# LT3798.net
KiCad netlist of a schematic drawn in Altium Designer
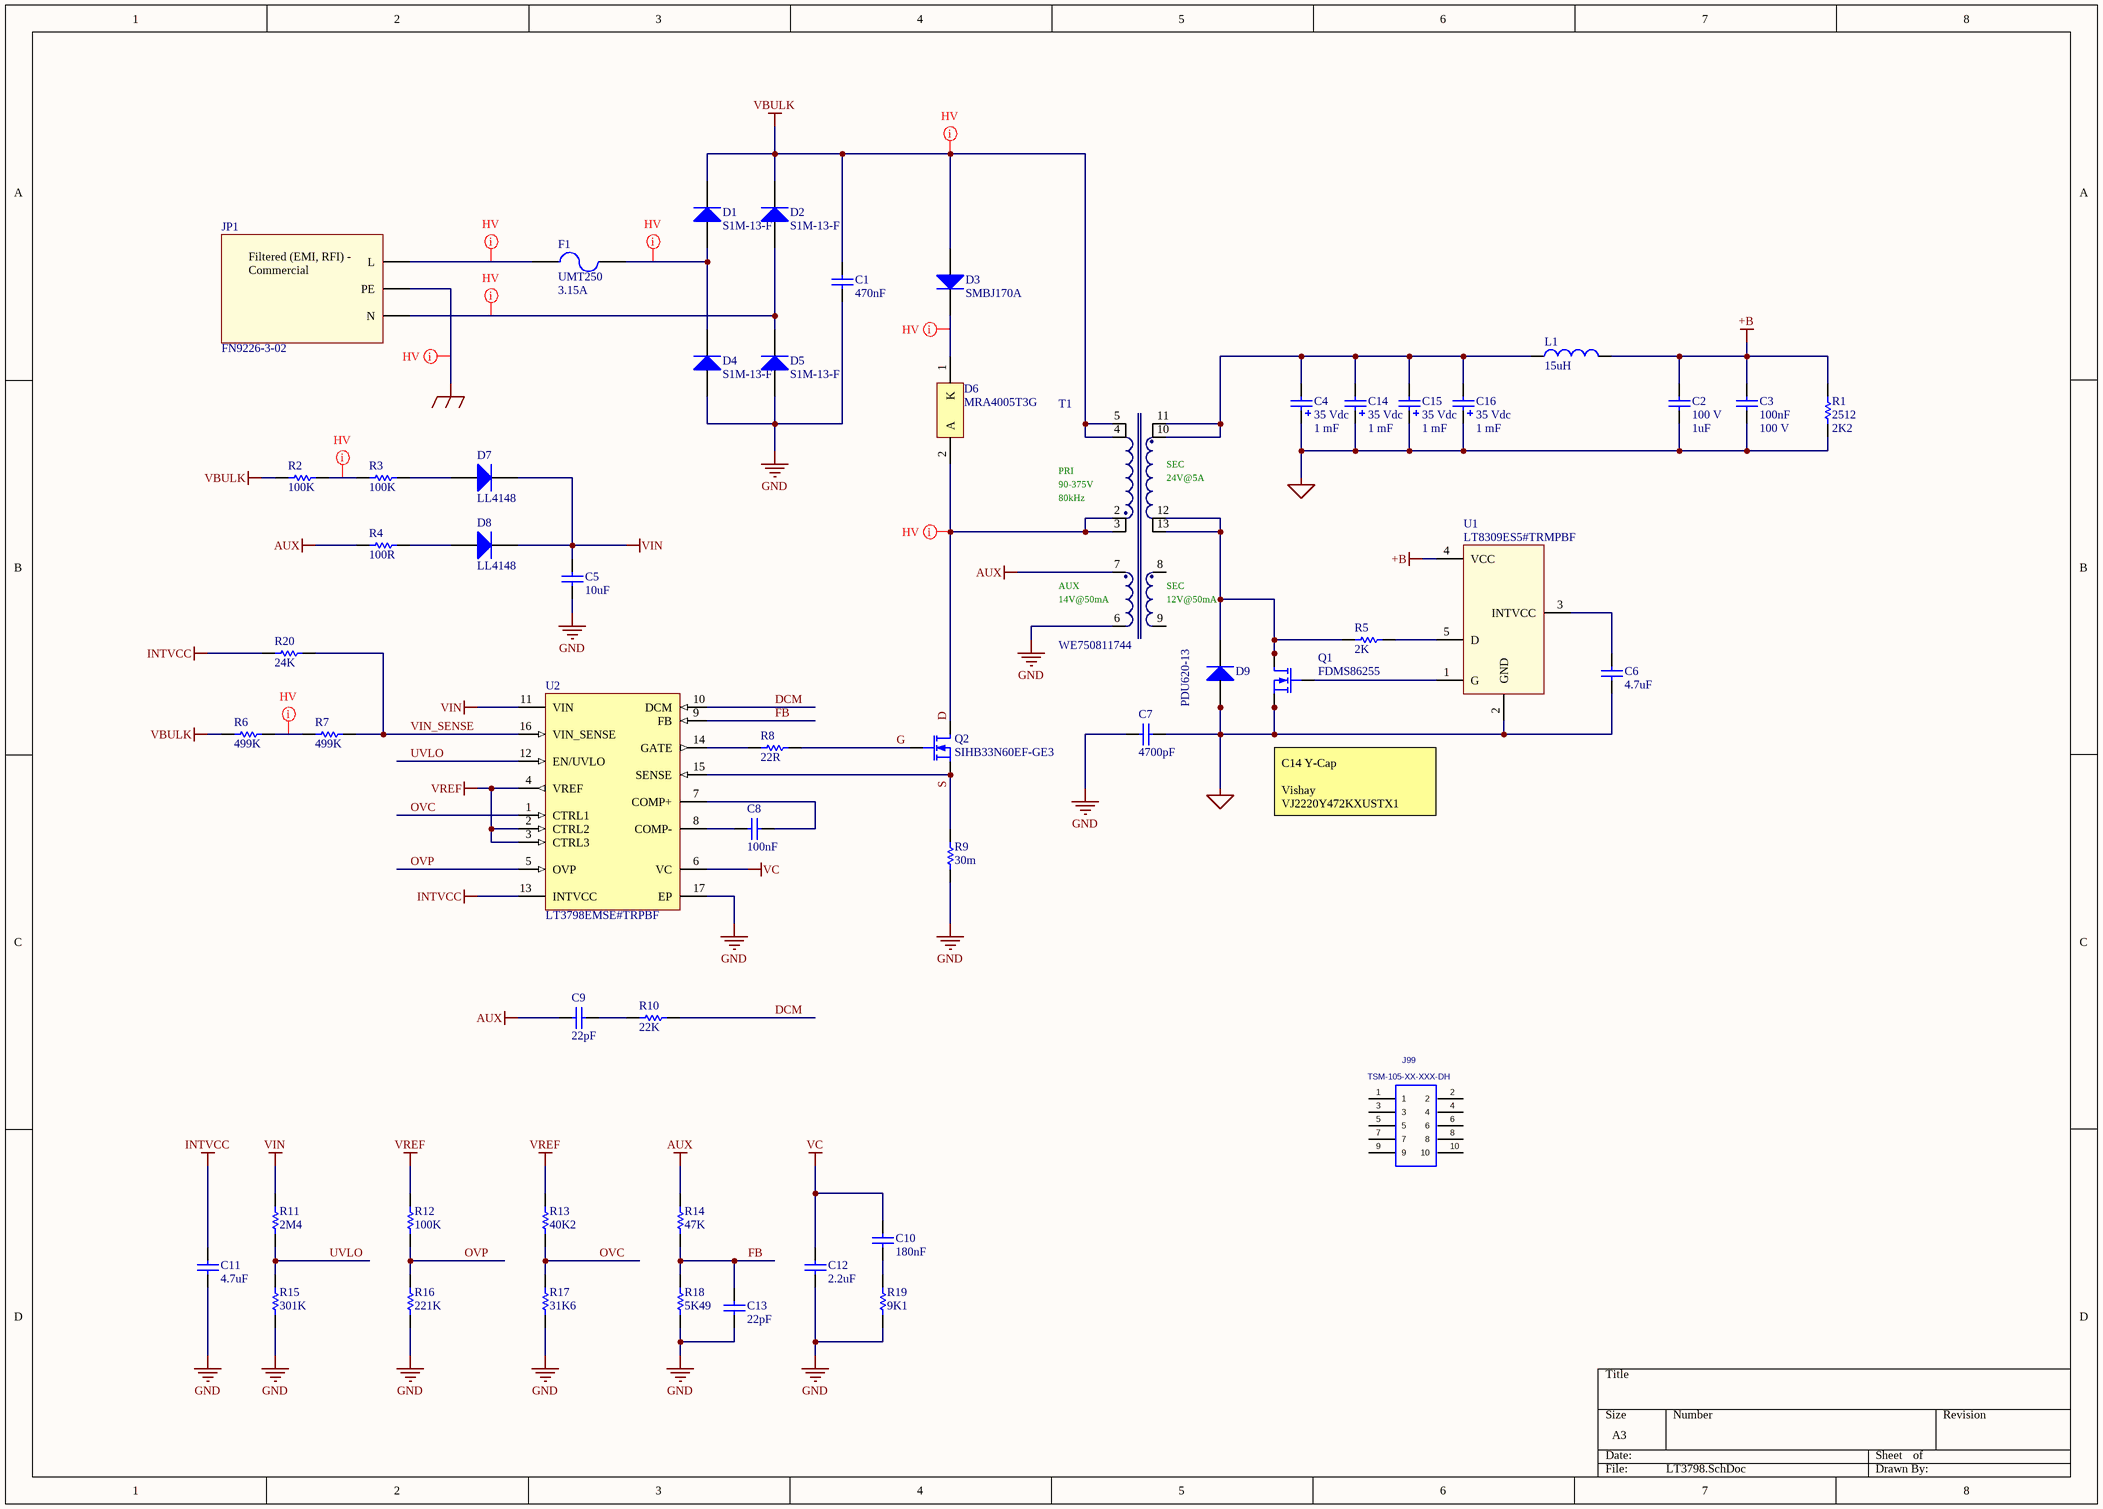
[diagram p0: LT3798.SchDoc]

(export (version "E")
  (design (tool "Eeschema 10.0.6"))
  (components
    (comp (ref "C1")
      (value "470nF")
      (footprint "CAP_RM15_W9L18")
      (description "CAP FILM 0.47UF 400VDC RADIAL")
      (fields (field (name "MPN") "B32652A4474J189"))
      (libsource (lib "micun") (part "CAP_FILM_470NF_400V"))
    )
    (comp (ref "C2")
      (value "1uF")
      (footprint "CAPC1206(3216)190_L")
      (description "CAP 1uF 100V ±20% 1206 (3216 Metric) Thickness 1.9mm SMD")
      (fields
        (field (name "RATED VOLTAGE") "100 V")
        (field (name "TOLERANCE") "Â±20%")
        (field (name "Comment") "CAP 1uF 100V 1206(3216)")
      )
      (libsource (lib "Altium Content Vault") (part "CAP"))
    )
    (comp (ref "C3")
      (value "100nF")
      (footprint "CAPC1206(3216)150_M")
      (description "CAP 100nF 100V ±20% 1206 (3216 Metric) Thickness 1.45mm SMD")
      (fields
        (field (name "TOLERANCE") "Â±20%")
        (field (name "RATED VOLTAGE") "100 V")
        (field (name "Comment") "CAP 100nF 100V 1206(3216)")
      )
      (libsource (lib "Altium Content Vault") (part "CAP"))
    )
    (comp (ref "C4")
      (value "1 mF")
      (footprint "WCAP-ATLL_10x30x5")
      (description "WCAP-ATLL Aluminum Electrolytic Capacitors, 10x30mm, 35 Vdc, 1 mF")
      (fields
        (field (name "PART NUMBER") "860160575031")
        (field (name "RATED VOLTAGE") "35 Vdc")
        (field (name "Comment") "35 Vdc, 1 mF")
        (field (name "PUBLISHER") "Wurth Elektronik")
      )
      (libsource (lib "ALTIUM-WCAP-ATLL-rev17a") (part "860160575031"))
    )
    (comp (ref "C5")
      (value "10uF")
      (footprint "CAPC0805(2012)75_N")
      (description "Generic capacitor non polarised")
      (fields (field (name "Comment") "CAP"))
      (libsource (lib "micun") (part "CAP"))
    )
    (comp (ref "C6")
      (value "4.7uF")
      (footprint "CAPC0805(2012)75_N")
      (description "Generic capacitor non polarised")
      (fields (field (name "Comment") "CAP"))
      (libsource (lib "micun") (part "CAP"))
    )
    (comp (ref "C7")
      (value "4700pF")
      (footprint "CAP_VY2472M49Y5US63V7")
      (description "4700pF ±20% 440VAC Ceramic Capacitor Y5U (E) Radial, Disc")
      (fields (field (name "MPN") "VY2472M49Y5US63V7") (field (name "VOLTAGE") "440VAC"))
      (libsource (lib "micun") (part "CAP_VY2_4700"))
    )
    (comp (ref "C8")
      (value "100nF")
      (footprint "CAPC0805(2012)75_N")
      (description "Generic capacitor non polarised")
      (fields (field (name "Comment") "CAP"))
      (libsource (lib "micun") (part "CAP"))
    )
    (comp (ref "C9")
      (value "22pF")
      (footprint "CAPC0805(2012)75_N")
      (description "Generic capacitor non polarised")
      (fields (field (name "Comment") "CAP"))
      (libsource (lib "micun") (part "CAP"))
    )
    (comp (ref "C10")
      (value "180nF")
      (footprint "CAPC0805(2012)75_N")
      (description "Generic capacitor non polarised")
      (fields (field (name "Comment") "CAP"))
      (libsource (lib "micun") (part "CAP"))
    )
    (comp (ref "C11")
      (value "4.7uF")
      (footprint "CAPC0805(2012)75_N")
      (description "Generic capacitor non polarised")
      (fields (field (name "Comment") "CAP"))
      (libsource (lib "micun") (part "CAP"))
    )
    (comp (ref "C12")
      (value "2.2uF")
      (footprint "CAPC0805(2012)75_N")
      (description "Generic capacitor non polarised")
      (fields (field (name "Comment") "CAP"))
      (libsource (lib "micun") (part "CAP"))
    )
    (comp (ref "C13")
      (value "22pF")
      (footprint "CAPC0805(2012)75_N")
      (description "Generic capacitor non polarised")
      (fields (field (name "Comment") "CAP"))
      (libsource (lib "micun") (part "CAP"))
    )
    (comp (ref "C14")
      (value "1 mF")
      (footprint "WCAP-ATLL_10x30x5")
      (description "WCAP-ATLL Aluminum Electrolytic Capacitors, 10x30mm, 35 Vdc, 1 mF")
      (fields
        (field (name "PART NUMBER") "860160575031")
        (field (name "RATED VOLTAGE") "35 Vdc")
        (field (name "Comment") "35 Vdc, 1 mF")
        (field (name "PUBLISHER") "Wurth Elektronik")
      )
      (libsource (lib "ALTIUM-WCAP-ATLL-rev17a") (part "860160575031"))
    )
    (comp (ref "C15")
      (value "1 mF")
      (footprint "WCAP-ATLL_10x30x5")
      (description "WCAP-ATLL Aluminum Electrolytic Capacitors, 10x30mm, 35 Vdc, 1 mF")
      (fields
        (field (name "PART NUMBER") "860160575031")
        (field (name "RATED VOLTAGE") "35 Vdc")
        (field (name "Comment") "35 Vdc, 1 mF")
        (field (name "PUBLISHER") "Wurth Elektronik")
      )
      (libsource (lib "ALTIUM-WCAP-ATLL-rev17a") (part "860160575031"))
    )
    (comp (ref "C16")
      (value "1 mF")
      (footprint "WCAP-ATLL_10x30x5")
      (description "WCAP-ATLL Aluminum Electrolytic Capacitors, 10x30mm, 35 Vdc, 1 mF")
      (fields
        (field (name "PART NUMBER") "860160575031")
        (field (name "RATED VOLTAGE") "35 Vdc")
        (field (name "Comment") "35 Vdc, 1 mF")
        (field (name "PUBLISHER") "Wurth Elektronik")
      )
      (libsource (lib "ALTIUM-WCAP-ATLL-rev17a") (part "860160575031"))
    )
    (comp (ref "D1")
      (value "S1M-13-F")
      (footprint "DIOD-S1M-13-F-SMA-2_V")
      (fields (field (name "MANUFACTURER") "Diodes Inc"))
      (libsource (lib "Altium Content Vault") (part "DIOD-D-A1K2-2"))
    )
    (comp (ref "D2")
      (value "S1M-13-F")
      (footprint "DIOD-S1M-13-F-SMA-2_V")
      (fields (field (name "MANUFACTURER") "Diodes Inc"))
      (libsource (lib "Altium Content Vault") (part "DIOD-D-A1K2-2"))
    )
    (comp (ref "D3")
      (value "SMBJ170A")
      (footprint "FAIR-DO-214AA-2_V")
      (description "TVS DIODE 170V 353V SMB")
      (fields (field (name "MANUFACTURER") "Fairchild Semiconductor"))
      (libsource (lib "micun") (part "TVS-SMBJ170A"))
    )
    (comp (ref "D4")
      (value "S1M-13-F")
      (footprint "DIOD-S1M-13-F-SMA-2_V")
      (fields (field (name "MANUFACTURER") "Diodes Inc"))
      (libsource (lib "Altium Content Vault") (part "DIOD-D-A1K2-2"))
    )
    (comp (ref "D5")
      (value "S1M-13-F")
      (footprint "DIOD-S1M-13-F-SMA-2_V")
      (fields (field (name "MANUFACTURER") "Diodes Inc"))
      (libsource (lib "Altium Content Vault") (part "DIOD-D-A1K2-2"))
    )
    (comp (ref "D6")
      (value "MRA4005T3G")
      (footprint "ONSC-SMA-2-403D-02_V")
      (description "Surface Mount Standard Recovery Power Rectifier, 2-Pin SMA, Pb-Free, Tape and Reel")
      (fields (field (name "MANUFACTURER") "On Semiconductor"))
      (libsource (lib "Altium Content Vault") (part "ONSC-D-K1A2-2_A"))
    )
    (comp (ref "D7")
      (value "LL4148")
      (footprint "DIOD-SOD-80")
      (description "DIODE GEN PURP 100V 200MA SOD80")
      (libsource (lib "micun") (part "DIOD_GP_LL4148"))
    )
    (comp (ref "D8")
      (value "LL4148")
      (footprint "DIOD-SOD-80")
      (description "DIODE GEN PURP 100V 200MA SOD80")
      (libsource (lib "micun") (part "DIOD_GP_LL4148"))
    )
    (comp (ref "D9")
      (value "PDU620-13")
      (footprint "PowerDI5")
      (description "Diode Standard 200V 6A Surface Mount PowerDI™ 5")
      (libsource (lib "micun") (part "DIOD_GP_PDU620-13"))
    )
    (comp (ref "F1")
      (value "UMT250")
      (footprint "FUSE_UMT250")
      (description "Fuse")
      (fields (field (name "MPN") "3403.0171.11") (field (name "ALTIUM_VALUE") "3.15A"))
      (libsource (lib "micun") (part "FUSE_UMT250-3.15A"))
    )
    (comp (ref "J99")
      (value "TSM-105-XX-XXX-DH")
      (footprint "TSM-105-XX-XXX-DH")
      (description "Terminal Strip, Dual Row Horizontal, Surface Mount, 0.100\" Pitch, 10 Pins.")
      (fields (field (name "MANUFACTURER") "SAMTEC") (field (name "CREATED") "July 11, 2014 - Wendy Xin"))
      (libsource (lib "micun") (part "CONN-TSM-105-XX-XXX-DH"))
    )
    (comp (ref "JP1")
      (value "FN9226-3-02")
      (footprint "CONN-FN9226-3-02")
      (libsource (lib "micun") (part "CONN_FN9226-3-02"))
    )
    (comp (ref "L1")
      (value "15uH")
      (footprint "1D14A")
      (description "Fixed Inductors Class D Inductor 15uH 16mOhms")
      (fields (field (name "MPN") "1D14A-150m"))
      (libsource (lib "micun") (part "L-1D14A-150m"))
    )
    (comp (ref "Q1")
      (value "FDMS86255")
      (footprint "POWER56")
      (description "N-Channel 150V 10A (Ta), 45A (Tc) 2.7W (Ta), 113W (Tc) Surface Mount Power56")
      (libsource (lib "micun") (part "TRAN_FDMS86255"))
    )
    (comp (ref "Q2")
      (value "SIHB33N60EF-GE3")
      (footprint "D2PAK_L")
      (description "N-Channel 600V 33A (Tc) 278W (Tc) Surface Mount D²PAK (TO-263)")
      (libsource (lib "micun") (part "TRAN_SIHB33N60EF-GE3"))
    )
    (comp (ref "R1")
      (value "2K2")
      (footprint "RESC2512(6432)_L")
      (description "2K2 1W 5% 2512 (6432 Metric)  SMD")
      (fields (field (name "POWER") "1 W") (field (name "CASE-EIA") "2512") (field (name "TOLERANCE") "5 %"))
      (libsource (lib "Altium Content Vault") (part "RES"))
    )
    (comp (ref "R2")
      (value "100K")
      (footprint "RESC1206(3216)_L")
      (description "100K 0.25W 1% 1206 (3216 Metric)  SMD")
      (fields (field (name "TOLERANCE") "1 %") (field (name "POWER") "0.25 W"))
      (libsource (lib "Altium Content Vault") (part "RES"))
    )
    (comp (ref "R3")
      (value "100K")
      (footprint "RESC1206(3216)_L")
      (description "100K 0.25W 1% 1206 (3216 Metric)  SMD")
      (fields (field (name "TOLERANCE") "1 %") (field (name "POWER") "0.25 W"))
      (libsource (lib "Altium Content Vault") (part "RES"))
    )
    (comp (ref "R4")
      (value "100R")
      (footprint "RESC0805(2012)_N")
      (description "Generic resistor")
      (fields (field (name "Comment") "RES"))
      (libsource (lib "micun") (part "RES"))
    )
    (comp (ref "R5")
      (value "2K")
      (footprint "RESC0805(2012)_N")
      (description "Generic resistor")
      (fields (field (name "Comment") "RES"))
      (libsource (lib "micun") (part "RES"))
    )
    (comp (ref "R6")
      (value "499K")
      (footprint "RESC1206(3216)_L")
      (description "499K 0.25W 1% 1206 (3216 Metric)  SMD")
      (fields (field (name "TOLERANCE") "1 %") (field (name "POWER") "0.25 W"))
      (libsource (lib "Altium Content Vault") (part "RES"))
    )
    (comp (ref "R7")
      (value "499K")
      (footprint "RESC1206(3216)_L")
      (description "499K 0.25W 1% 1206 (3216 Metric)  SMD")
      (fields (field (name "TOLERANCE") "1 %") (field (name "POWER") "0.25 W"))
      (libsource (lib "Altium Content Vault") (part "RES"))
    )
    (comp (ref "R8")
      (value "22R")
      (footprint "RESC0805(2012)_L")
      (description "22R 0.125W 5% 0805 (2012 Metric)  SMD")
      (fields (field (name "POWER") "0.125 W") (field (name "TOLERANCE") "5 %"))
      (libsource (lib "Altium Content Vault") (part "RES"))
    )
    (comp (ref "R9")
      (value "30m")
      (footprint "RESC1206(3216)_N")
      (description "Generic resistor")
      (fields (field (name "Comment") "RES"))
      (libsource (lib "micun") (part "RES"))
    )
    (comp (ref "R10")
      (value "22K")
      (footprint "RESC0805(2012)_L")
      (description "22K 0.125W 5% 0805 (2012 Metric)  SMD")
      (fields (field (name "POWER") "0.125 W") (field (name "TOLERANCE") "5 %"))
      (libsource (lib "Altium Content Vault") (part "RES"))
    )
    (comp (ref "R11")
      (value "2M4")
      (footprint "RESC0805(2012)_L")
      (description "2M4 0.125W 1% 0805 (2012 Metric)  SMD")
      (fields (field (name "TOLERANCE") "1 %") (field (name "POWER") "0.125 W"))
      (libsource (lib "Altium Content Vault") (part "RES"))
    )
    (comp (ref "R12")
      (value "100K")
      (footprint "RESC0805(2012)_L")
      (description "100K 0.125W 1% 0805 (2012 Metric)  SMD")
      (fields (field (name "TOLERANCE") "1 %") (field (name "POWER") "0.125 W"))
      (libsource (lib "Altium Content Vault") (part "RES"))
    )
    (comp (ref "R13")
      (value "40K2")
      (footprint "RESC0805(2012)_L")
      (description "40K2 0.125W 1% 0805 (2012 Metric)  SMD")
      (fields (field (name "TOLERANCE") "1 %") (field (name "POWER") "0.125 W"))
      (libsource (lib "Altium Content Vault") (part "RES"))
    )
    (comp (ref "R14")
      (value "47K")
      (footprint "RESC0805(2012)_N")
      (description "Generic resistor")
      (fields (field (name "Comment") "RES"))
      (libsource (lib "micun") (part "RES"))
    )
    (comp (ref "R15")
      (value "301K")
      (footprint "RESC0805(2012)_L")
      (description "301K 0.125W 1% 0805 (2012 Metric)  SMD")
      (fields (field (name "TOLERANCE") "1 %") (field (name "POWER") "0.125 W"))
      (libsource (lib "Altium Content Vault") (part "RES"))
    )
    (comp (ref "R16")
      (value "221K")
      (footprint "RESC0805(2012)_L")
      (description "221K 0.125W 1% 0805 (2012 Metric)  SMD")
      (fields (field (name "TOLERANCE") "1 %") (field (name "POWER") "0.125 W"))
      (libsource (lib "Altium Content Vault") (part "RES"))
    )
    (comp (ref "R17")
      (value "31K6")
      (footprint "RESC0805(2012)_L")
      (description "31K6 0.125W 1% 0805 (2012 Metric)  SMD")
      (fields (field (name "TOLERANCE") "1 %") (field (name "POWER") "0.125 W"))
      (libsource (lib "Altium Content Vault") (part "RES"))
    )
    (comp (ref "R18")
      (value "5K49")
      (footprint "RESC0805(2012)_N")
      (description "Generic resistor")
      (fields (field (name "Comment") "RES"))
      (libsource (lib "micun") (part "RES"))
    )
    (comp (ref "R19")
      (value "9K1")
      (footprint "RESC0805(2012)_N")
      (description "Generic resistor")
      (fields (field (name "Comment") "RES"))
      (libsource (lib "micun") (part "RES"))
    )
    (comp (ref "R20")
      (value "24K")
      (footprint "RESC0805(2012)_N")
      (description "24K 0.125W 5% 0805 (2012 Metric)  SMD")
      (fields (field (name "POWER") "0.125 W") (field (name "TOLERANCE") "5 %"))
      (libsource (lib "Altium Content Vault") (part "RES"))
    )
    (comp (ref "T1")
      (value "WE750811744")
      (footprint "ETD34_5455")
      (description "MID-OLLT Offline Flyback Transformers for Linear Technology")
      (fields (field (name "MPN") "750811744"))
      (libsource (lib "micun") (part "TRANS_WE750811744"))
    )
    (comp (ref "U1")
      (value "LT8309ES5#TRMPBF")
      (footprint "SOT23-5_L")
      (libsource (lib "micun") (part "IC-PMIC-LT8309"))
    )
    (comp (ref "U2")
      (value "LT3798EMSE#TRPBF")
      (footprint "LT-MSE-16-EDP_N")
      (fields (field (name "MANUFACTURER") "Linear Technology"))
      (libsource (lib "Altium Content Vault") (part "LT-LT3798-MSE-16"))
    )
  )
  (nets
    (net (code "1") (name "+B") (class "Default")
      (node (ref "C2") (pin "2") (pinfunction "2_2") (pintype "passive"))
      (node (ref "C3") (pin "2") (pinfunction "2_2") (pintype "passive"))
      (node (ref "L1") (pin "2") (pinfunction "2_2") (pintype "passive"))
      (node (ref "R1") (pin "2") (pinfunction "2_2") (pintype "passive"))
      (node (ref "U1") (pin "4") (pinfunction "VCC_4") (pintype "power_in"))
    )
    (net (code "2") (name "/D") (class "Default")
      (node (ref "D6") (pin "2") (pinfunction "A_2") (pintype "passive"))
      (node (ref "Q2") (pin "4") (pinfunction "D_4") (pintype "passive"))
      (node (ref "T1") (pin "2") (pinfunction "2_2") (pintype "passive"))
      (node (ref "T1") (pin "3") (pinfunction "3_3") (pintype "passive"))
    )
    (net (code "3") (name "/DCM") (class "Default")
      (node (ref "R10") (pin "2") (pinfunction "2_2") (pintype "passive"))
      (node (ref "U2") (pin "10") (pinfunction "DCM_10") (pintype "input"))
    )
    (net (code "4") (name "/FB") (class "Default")
      (node (ref "C13") (pin "2") (pinfunction "2_2") (pintype "passive"))
      (node (ref "R14") (pin "1") (pinfunction "1_1") (pintype "passive"))
      (node (ref "R18") (pin "2") (pinfunction "2_2") (pintype "passive"))
      (node (ref "U2") (pin "9") (pinfunction "FB_9") (pintype "input"))
    )
    (net (code "5") (name "/G") (class "Default")
      (node (ref "Q2") (pin "1") (pinfunction "G_1") (pintype "passive"))
      (node (ref "R8") (pin "2") (pinfunction "2_2") (pintype "passive"))
    )
    (net (code "6") (name "/OVC") (class "Default")
      (node (ref "R13") (pin "1") (pinfunction "1_1") (pintype "passive"))
      (node (ref "R17") (pin "2") (pinfunction "2_2") (pintype "passive"))
      (node (ref "U2") (pin "1") (pinfunction "CTRL1_1") (pintype "input"))
    )
    (net (code "7") (name "/OVP") (class "Default")
      (node (ref "R12") (pin "1") (pinfunction "1_1") (pintype "passive"))
      (node (ref "R16") (pin "2") (pinfunction "2_2") (pintype "passive"))
      (node (ref "U2") (pin "5") (pinfunction "OVP_5") (pintype "input"))
    )
    (net (code "8") (name "/S") (class "Default")
      (node (ref "Q2") (pin "3") (pinfunction "S_3") (pintype "passive"))
      (node (ref "R9") (pin "2") (pinfunction "2_2") (pintype "passive"))
      (node (ref "U2") (pin "15") (pinfunction "SENSE_15") (pintype "input"))
    )
    (net (code "9") (name "/UVLO") (class "Default")
      (node (ref "R11") (pin "1") (pinfunction "1_1") (pintype "passive"))
      (node (ref "R15") (pin "2") (pinfunction "2_2") (pintype "passive"))
      (node (ref "U2") (pin "12") (pinfunction "EN/UVLO_12") (pintype "input"))
    )
    (net (code "10") (name "/VIN_SENSE") (class "Default")
      (node (ref "R20") (pin "2") (pinfunction "2_2") (pintype "passive"))
      (node (ref "R7") (pin "2") (pinfunction "2_2") (pintype "passive"))
      (node (ref "U2") (pin "16") (pinfunction "VIN_SENSE_16") (pintype "input"))
    )
    (net (code "11") (name "AUX") (class "Default")
      (node (ref "C9") (pin "2") (pinfunction "2_2") (pintype "passive"))
      (node (ref "R14") (pin "2") (pinfunction "2_2") (pintype "passive"))
      (node (ref "R4") (pin "2") (pinfunction "2_2") (pintype "passive"))
      (node (ref "T1") (pin "7") (pinfunction "7_7") (pintype "passive"))
    )
    (net (code "12") (name "GND") (class "Default")
      (node (ref "C1") (pin "1") (pinfunction "1_1") (pintype "passive"))
      (node (ref "C11") (pin "1") (pinfunction "1_1") (pintype "passive"))
      (node (ref "C12") (pin "1") (pinfunction "1_1") (pintype "passive"))
      (node (ref "C13") (pin "1") (pinfunction "1_1") (pintype "passive"))
      (node (ref "C5") (pin "1") (pinfunction "1_1") (pintype "passive"))
      (node (ref "C7") (pin "1") (pinfunction "1_1") (pintype "passive"))
      (node (ref "D4") (pin "1") (pinfunction "A_1") (pintype "passive"))
      (node (ref "D5") (pin "1") (pinfunction "A_1") (pintype "passive"))
      (node (ref "R15") (pin "1") (pinfunction "1_1") (pintype "passive"))
      (node (ref "R16") (pin "1") (pinfunction "1_1") (pintype "passive"))
      (node (ref "R17") (pin "1") (pinfunction "1_1") (pintype "passive"))
      (node (ref "R18") (pin "1") (pinfunction "1_1") (pintype "passive"))
      (node (ref "R19") (pin "1") (pinfunction "1_1") (pintype "passive"))
      (node (ref "R9") (pin "1") (pinfunction "1_1") (pintype "passive"))
      (node (ref "T1") (pin "6") (pinfunction "6_6") (pintype "passive"))
      (node (ref "U2") (pin "17") (pinfunction "EP_17") (pintype "power_in"))
    )
    (net (code "13") (name "INTVCC") (class "Default")
      (node (ref "C11") (pin "2") (pinfunction "2_2") (pintype "passive"))
      (node (ref "R20") (pin "1") (pinfunction "1_1") (pintype "passive"))
      (node (ref "U2") (pin "13") (pinfunction "INTVCC_13") (pintype "power_in"))
    )
    (net (code "14") (name "Net-(C9-Pad1)") (class "Default")
      (node (ref "C9") (pin "1") (pinfunction "1_1") (pintype "passive"))
      (node (ref "R10") (pin "1") (pinfunction "1_1") (pintype "passive"))
    )
    (net (code "15") (name "Net-(C10-Pad1)") (class "Default")
      (node (ref "C10") (pin "1") (pinfunction "1_1") (pintype "passive"))
      (node (ref "R19") (pin "2") (pinfunction "2_2") (pintype "passive"))
    )
    (net (code "16") (name "Net-(C14-N)") (class "Default")
      (node (ref "C14") (pin "2") (pinfunction "N_2") (pintype "passive"))
      (node (ref "C15") (pin "2") (pinfunction "N_2") (pintype "passive"))
      (node (ref "C16") (pin "2") (pinfunction "N_2") (pintype "passive"))
      (node (ref "C4") (pin "2") (pinfunction "N_2") (pintype "passive"))
      (node (ref "L1") (pin "1") (pinfunction "1_1") (pintype "passive"))
      (node (ref "T1") (pin "10") (pinfunction "10_10") (pintype "passive"))
      (node (ref "T1") (pin "11") (pinfunction "11_11") (pintype "passive"))
    )
    (net (code "17") (name "Net-(D1-A)") (class "Default")
      (node (ref "D1") (pin "1") (pinfunction "A_1") (pintype "passive"))
      (node (ref "D4") (pin "2") (pinfunction "K_2") (pintype "passive"))
      (node (ref "F1") (pin "2") (pinfunction "2_2") (pintype "passive"))
    )
    (net (code "18") (name "Net-(D2-A)") (class "Default")
      (node (ref "D2") (pin "1") (pinfunction "A_1") (pintype "passive"))
      (node (ref "D5") (pin "2") (pinfunction "K_2") (pintype "passive"))
      (node (ref "JP1") (pin "N") (pinfunction "N_N") (pintype "power_in"))
    )
    (net (code "19") (name "Net-(D3-K)") (class "Default")
      (node (ref "D3") (pin "2") (pinfunction "K_2") (pintype "passive"))
      (node (ref "D6") (pin "1") (pinfunction "K_1") (pintype "passive"))
    )
    (net (code "20") (name "Net-(D7-A)") (class "Default")
      (node (ref "D7") (pin "1") (pinfunction "A_1") (pintype "passive"))
      (node (ref "R3") (pin "2") (pinfunction "2_2") (pintype "passive"))
    )
    (net (code "21") (name "Net-(D8-A)") (class "Default")
      (node (ref "D8") (pin "1") (pinfunction "A_1") (pintype "passive"))
      (node (ref "R4") (pin "1") (pinfunction "1_1") (pintype "passive"))
    )
    (net (code "22") (name "Net-(D9-K)") (class "Default")
      (node (ref "D9") (pin "3") (pinfunction "K_3") (pintype "passive"))
      (node (ref "Q1") (pin "5") (pinfunction "D_5") (pintype "passive"))
      (node (ref "Q1") (pin "6") (pinfunction "D_6") (pintype "passive"))
      (node (ref "Q1") (pin "7") (pinfunction "D_7") (pintype "passive"))
      (node (ref "Q1") (pin "8") (pinfunction "D_8") (pintype "passive"))
      (node (ref "Q1") (pin "EP") (pinfunction "D_EP") (pintype "passive"))
      (node (ref "R5") (pin "1") (pinfunction "1_1") (pintype "passive"))
      (node (ref "T1") (pin "12") (pinfunction "12_12") (pintype "passive"))
      (node (ref "T1") (pin "13") (pinfunction "13_13") (pintype "passive"))
    )
    (net (code "23") (name "Net-(F1-Pad1)") (class "Default")
      (node (ref "F1") (pin "1") (pinfunction "1_1") (pintype "passive"))
      (node (ref "JP1") (pin "L") (pinfunction "L_L") (pintype "power_in"))
    )
    (net (code "24") (name "Net-(Q1-G)") (class "Default")
      (node (ref "Q1") (pin "4") (pinfunction "G_4") (pintype "passive"))
      (node (ref "U1") (pin "1") (pinfunction "G_1") (pintype "passive"))
    )
    (net (code "25") (name "Net-(R2-Pad2)") (class "Default")
      (node (ref "R2") (pin "2") (pinfunction "2_2") (pintype "passive"))
      (node (ref "R3") (pin "1") (pinfunction "1_1") (pintype "passive"))
    )
    (net (code "26") (name "Net-(R6-Pad2)") (class "Default")
      (node (ref "R6") (pin "2") (pinfunction "2_2") (pintype "passive"))
      (node (ref "R7") (pin "1") (pinfunction "1_1") (pintype "passive"))
    )
    (net (code "27") (name "Net-(U1-D)") (class "Default")
      (node (ref "R5") (pin "2") (pinfunction "2_2") (pintype "passive"))
      (node (ref "U1") (pin "5") (pinfunction "D_5") (pintype "passive"))
    )
    (net (code "28") (name "Net-(U1-INTVCC)") (class "Default")
      (node (ref "C6") (pin "2") (pinfunction "2_2") (pintype "passive"))
      (node (ref "U1") (pin "3") (pinfunction "INTVCC_3") (pintype "power_in"))
    )
    (net (code "29") (name "Net-(U2-COMP+)") (class "Default")
      (node (ref "C8") (pin "1") (pinfunction "1_1") (pintype "passive"))
      (node (ref "U2") (pin "7") (pinfunction "COMP+_7") (pintype "passive"))
    )
    (net (code "30") (name "Net-(U2-COMP-)") (class "Default")
      (node (ref "C8") (pin "2") (pinfunction "2_2") (pintype "passive"))
      (node (ref "U2") (pin "8") (pinfunction "COMP-_8") (pintype "passive"))
    )
    (net (code "31") (name "Net-(U2-GATE)") (class "Default")
      (node (ref "R8") (pin "1") (pinfunction "1_1") (pintype "passive"))
      (node (ref "U2") (pin "14") (pinfunction "GATE_14") (pintype "output"))
    )
    (net (code "32") (name "PE") (class "Default")
      (node (ref "JP1") (pin "PE") (pinfunction "PE_PE") (pintype "power_in"))
    )
    (net (code "33") (name "SGND") (class "Default")
      (node (ref "C14") (pin "1") (pinfunction "P_1") (pintype "passive"))
      (node (ref "C15") (pin "1") (pinfunction "P_1") (pintype "passive"))
      (node (ref "C16") (pin "1") (pinfunction "P_1") (pintype "passive"))
      (node (ref "C2") (pin "1") (pinfunction "1_1") (pintype "passive"))
      (node (ref "C3") (pin "1") (pinfunction "1_1") (pintype "passive"))
      (node (ref "C4") (pin "1") (pinfunction "P_1") (pintype "passive"))
      (node (ref "C6") (pin "1") (pinfunction "1_1") (pintype "passive"))
      (node (ref "C7") (pin "2") (pinfunction "2_2") (pintype "passive"))
      (node (ref "D9") (pin "1") (pinfunction "A1_1") (pintype "passive"))
      (node (ref "D9") (pin "2") (pinfunction "A2_2") (pintype "passive"))
      (node (ref "Q1") (pin "1") (pinfunction "S_1") (pintype "passive"))
      (node (ref "Q1") (pin "2") (pinfunction "S_2") (pintype "passive"))
      (node (ref "Q1") (pin "3") (pinfunction "S_3") (pintype "passive"))
      (node (ref "R1") (pin "1") (pinfunction "1_1") (pintype "passive"))
      (node (ref "U1") (pin "2") (pinfunction "GND_2") (pintype "passive"))
    )
    (net (code "34") (name "VBULK") (class "Default")
      (node (ref "C1") (pin "2") (pinfunction "2_2") (pintype "passive"))
      (node (ref "D1") (pin "2") (pinfunction "K_2") (pintype "passive"))
      (node (ref "D2") (pin "2") (pinfunction "K_2") (pintype "passive"))
      (node (ref "D3") (pin "1") (pinfunction "A_1") (pintype "passive"))
      (node (ref "R2") (pin "1") (pinfunction "1_1") (pintype "passive"))
      (node (ref "R6") (pin "1") (pinfunction "1_1") (pintype "passive"))
      (node (ref "T1") (pin "4") (pinfunction "4_4") (pintype "passive"))
      (node (ref "T1") (pin "5") (pinfunction "5_5") (pintype "passive"))
    )
    (net (code "35") (name "VC") (class "Default")
      (node (ref "C10") (pin "2") (pinfunction "2_2") (pintype "passive"))
      (node (ref "C12") (pin "2") (pinfunction "2_2") (pintype "passive"))
      (node (ref "U2") (pin "6") (pinfunction "VC_6") (pintype "passive"))
    )
    (net (code "36") (name "VIN") (class "Default")
      (node (ref "C5") (pin "2") (pinfunction "2_2") (pintype "passive"))
      (node (ref "D7") (pin "2") (pinfunction "K_2") (pintype "passive"))
      (node (ref "D8") (pin "2") (pinfunction "K_2") (pintype "passive"))
      (node (ref "R11") (pin "2") (pinfunction "2_2") (pintype "passive"))
      (node (ref "U2") (pin "11") (pinfunction "VIN_11") (pintype "power_in"))
    )
    (net (code "37") (name "VREF") (class "Default")
      (node (ref "R12") (pin "2") (pinfunction "2_2") (pintype "passive"))
      (node (ref "R13") (pin "2") (pinfunction "2_2") (pintype "passive"))
      (node (ref "U2") (pin "2") (pinfunction "CTRL2_2") (pintype "input"))
      (node (ref "U2") (pin "3") (pinfunction "CTRL3_3") (pintype "input"))
      (node (ref "U2") (pin "4") (pinfunction "VREF_4") (pintype "output"))
    )
    (net (code "38") (name "unconnected-(J99-Pad1)") (class "Default")
      (node (ref "J99") (pin "1") (pinfunction "1_1") (pintype "passive"))
    )
    (net (code "39") (name "unconnected-(J99-Pad2)") (class "Default")
      (node (ref "J99") (pin "2") (pinfunction "2_2") (pintype "passive"))
    )
    (net (code "40") (name "unconnected-(J99-Pad3)") (class "Default")
      (node (ref "J99") (pin "3") (pinfunction "3_3") (pintype "passive"))
    )
    (net (code "41") (name "unconnected-(J99-Pad4)") (class "Default")
      (node (ref "J99") (pin "4") (pinfunction "4_4") (pintype "passive"))
    )
    (net (code "42") (name "unconnected-(J99-Pad5)") (class "Default")
      (node (ref "J99") (pin "5") (pinfunction "5_5") (pintype "passive"))
    )
    (net (code "43") (name "unconnected-(J99-Pad6)") (class "Default")
      (node (ref "J99") (pin "6") (pinfunction "6_6") (pintype "passive"))
    )
    (net (code "44") (name "unconnected-(J99-Pad7)") (class "Default")
      (node (ref "J99") (pin "7") (pinfunction "7_7") (pintype "passive"))
    )
    (net (code "45") (name "unconnected-(J99-Pad8)") (class "Default")
      (node (ref "J99") (pin "8") (pinfunction "8_8") (pintype "passive"))
    )
    (net (code "46") (name "unconnected-(J99-Pad9)") (class "Default")
      (node (ref "J99") (pin "9") (pinfunction "9_9") (pintype "passive"))
    )
    (net (code "47") (name "unconnected-(J99-Pad10)") (class "Default")
      (node (ref "J99") (pin "10") (pinfunction "10_10") (pintype "passive"))
    )
    (net (code "48") (name "unconnected-(T1-Pad8)") (class "Default")
      (node (ref "T1") (pin "8") (pinfunction "8_8") (pintype "passive"))
    )
    (net (code "49") (name "unconnected-(T1-Pad9)") (class "Default")
      (node (ref "T1") (pin "9") (pinfunction "9_9") (pintype "passive"))
    )
  )
)
